# DM04r.net
KiCad netlist of a schematic drawn in EAGLE
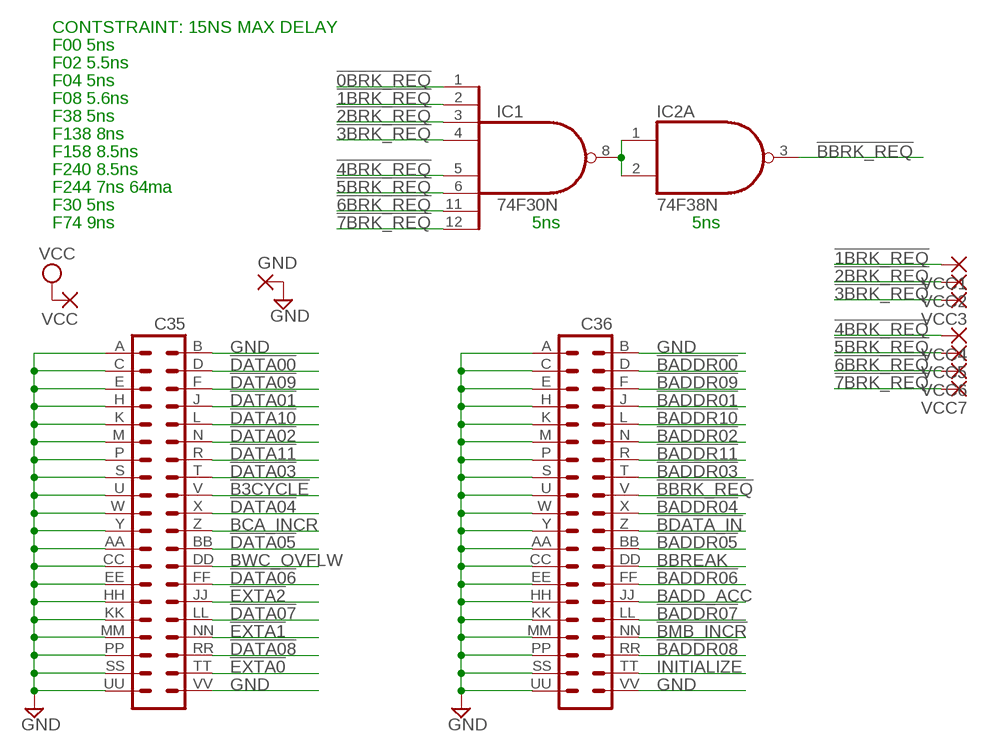
[diagram p0: schematic, sheet 1]
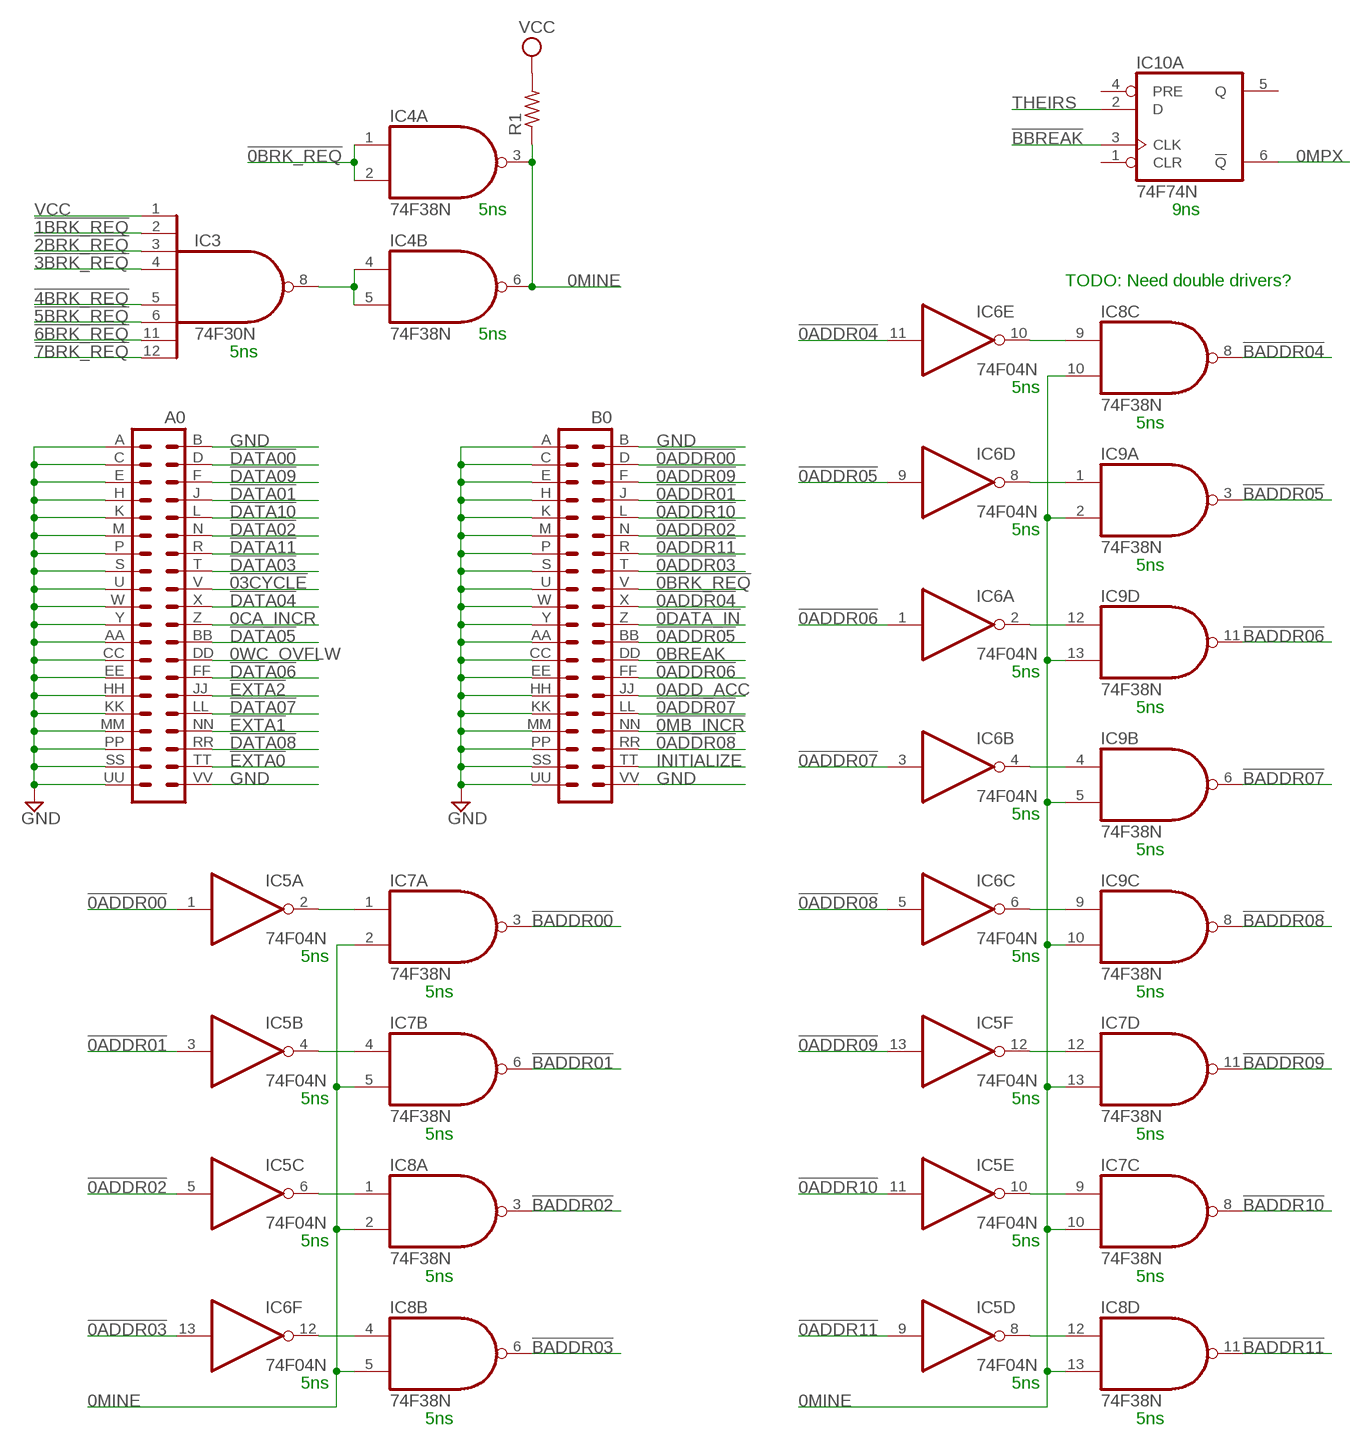
[diagram p1: schematic, sheet 2]

(export (version "E")
  (design (tool "Eeschema 10.0.6"))
  (components
    (comp (ref "C35")
      (value "DEC40PINV")
      (footprint "eagle-import:DEC40PINV")
      (libsource (lib "eagle-import") (part "DEC40PINV"))
    )
    (comp (ref "C36")
      (value "DEC40PINV")
      (footprint "eagle-import:DEC40PINV")
      (libsource (lib "eagle-import") (part "DEC40PINV"))
    )
    (comp (ref "GND")
      (value "2,54/0,8")
      (footprint "eagle-import:2,54_0,8")
      (libsource (lib "eagle-import") (part "2,54/0,8"))
    )
    (comp (ref "IC1")
      (value "74F30N")
      (footprint "eagle-import:DIL14")
      (libsource (lib "eagle-import") (part "7430NS"))
    )
    (comp (ref "IC2")
      (value "74F38N")
      (footprint "eagle-import:DIL14")
      (libsource (lib "eagle-import") (part "7438NF"))
    )
    (comp (ref "VCC")
      (value "2,54/0,8")
      (footprint "eagle-import:2,54_0,8")
      (libsource (lib "eagle-import") (part "2,54/0,8"))
    )
    (comp (ref "VCC1")
      (value "2,54/0,8")
      (footprint "eagle-import:2,54_0,8")
      (libsource (lib "eagle-import") (part "2,54/0,8"))
    )
    (comp (ref "VCC2")
      (value "2,54/0,8")
      (footprint "eagle-import:2,54_0,8")
      (libsource (lib "eagle-import") (part "2,54/0,8"))
    )
    (comp (ref "VCC3")
      (value "2,54/0,8")
      (footprint "eagle-import:2,54_0,8")
      (libsource (lib "eagle-import") (part "2,54/0,8"))
    )
    (comp (ref "VCC4")
      (value "2,54/0,8")
      (footprint "eagle-import:2,54_0,8")
      (libsource (lib "eagle-import") (part "2,54/0,8"))
    )
    (comp (ref "VCC5")
      (value "2,54/0,8")
      (footprint "eagle-import:2,54_0,8")
      (libsource (lib "eagle-import") (part "2,54/0,8"))
    )
    (comp (ref "VCC6")
      (value "2,54/0,8")
      (footprint "eagle-import:2,54_0,8")
      (libsource (lib "eagle-import") (part "2,54/0,8"))
    )
    (comp (ref "VCC7")
      (value "2,54/0,8")
      (footprint "eagle-import:2,54_0,8")
      (libsource (lib "eagle-import") (part "2,54/0,8"))
    )
    (comp (ref "A0")
      (value "DEC40PINV")
      (footprint "eagle-import:DEC40PINV")
      (libsource (lib "eagle-import") (part "DEC40PINV"))
    )
    (comp (ref "B0")
      (value "DEC40PINV")
      (footprint "eagle-import:DEC40PINV")
      (libsource (lib "eagle-import") (part "DEC40PINV"))
    )
    (comp (ref "IC3")
      (value "74F30N")
      (footprint "eagle-import:DIL14")
      (libsource (lib "eagle-import") (part "7430NS"))
    )
    (comp (ref "IC4")
      (value "74F38N")
      (footprint "eagle-import:DIL14")
      (libsource (lib "eagle-import") (part "7438NF"))
    )
    (comp (ref "IC5")
      (value "74F04N")
      (footprint "eagle-import:DIL14")
      (libsource (lib "eagle-import") (part "7404NS"))
    )
    (comp (ref "IC6")
      (value "74F04N")
      (footprint "eagle-import:DIL14")
      (libsource (lib "eagle-import") (part "7404NS"))
    )
    (comp (ref "IC7")
      (value "74F38N")
      (footprint "eagle-import:DIL14")
      (libsource (lib "eagle-import") (part "7438NF"))
    )
    (comp (ref "IC8")
      (value "74F38N")
      (footprint "eagle-import:DIL14")
      (libsource (lib "eagle-import") (part "7438NF"))
    )
    (comp (ref "IC9")
      (value "74F38N")
      (footprint "eagle-import:DIL14")
      (libsource (lib "eagle-import") (part "7438NF"))
    )
    (comp (ref "IC10")
      (value "74F74N")
      (footprint "eagle-import:DIL14")
      (libsource (lib "eagle-import") (part "7474NS"))
    )
    (comp (ref "R1")
      (value "R-US_0207/10")
      (footprint "eagle-import:0207_10")
      (libsource (lib "eagle-import") (part "R-US_0207/10"))
    )
  )
  (nets
    (net (code "1") (name "0ADD_ACC") (class "Default")
      (node (ref "B0") (pin "JJ") (pinfunction "30_JJ") (pintype "bidirectional"))
    )
    (net (code "2") (name "0BREAK") (class "Default")
      (node (ref "B0") (pin "DD") (pinfunction "26_DD") (pintype "bidirectional"))
    )
    (net (code "3") (name "0CA_INCR") (class "Default")
      (node (ref "A0") (pin "Z") (pinfunction "22_Z") (pintype "bidirectional"))
    )
    (net (code "4") (name "0MINE") (class "Default")
      (node (ref "IC4") (pin "3") (pinfunction "O_3") (pintype "open_collector"))
      (node (ref "IC4") (pin "6") (pinfunction "O_6") (pintype "open_collector"))
      (node (ref "IC7") (pin "10") (pinfunction "I1_10") (pintype "input"))
      (node (ref "IC7") (pin "13") (pinfunction "I1_13") (pintype "input"))
      (node (ref "IC7") (pin "2") (pinfunction "I1_2") (pintype "input"))
      (node (ref "IC7") (pin "5") (pinfunction "I1_5") (pintype "input"))
      (node (ref "IC8") (pin "10") (pinfunction "I1_10") (pintype "input"))
      (node (ref "IC8") (pin "13") (pinfunction "I1_13") (pintype "input"))
      (node (ref "IC8") (pin "2") (pinfunction "I1_2") (pintype "input"))
      (node (ref "IC8") (pin "5") (pinfunction "I1_5") (pintype "input"))
      (node (ref "IC9") (pin "10") (pinfunction "I1_10") (pintype "input"))
      (node (ref "IC9") (pin "13") (pinfunction "I1_13") (pintype "input"))
      (node (ref "IC9") (pin "2") (pinfunction "I1_2") (pintype "input"))
      (node (ref "IC9") (pin "5") (pinfunction "I1_5") (pintype "input"))
      (node (ref "R1") (pin "1") (pinfunction "1_1") (pintype "passive"))
    )
    (net (code "5") (name "0MPX") (class "Default")
      (node (ref "IC10") (pin "6") (pinfunction "~{Q}_6") (pintype "output"))
    )
    (net (code "6") (name "0WC_OVFLW") (class "Default")
      (node (ref "A0") (pin "DD") (pinfunction "26_DD") (pintype "bidirectional"))
    )
    (net (code "7") (name "BADD_ACC") (class "Default")
      (node (ref "C36") (pin "JJ") (pinfunction "30_JJ") (pintype "bidirectional"))
    )
    (net (code "8") (name "BBREAK") (class "Default")
      (node (ref "C36") (pin "DD") (pinfunction "26_DD") (pintype "bidirectional"))
    )
    (net (code "9") (name "BCA_INCR") (class "Default")
      (node (ref "C35") (pin "Z") (pinfunction "22_Z") (pintype "bidirectional"))
    )
    (net (code "10") (name "BWC_OVFLW") (class "Default")
      (node (ref "C35") (pin "DD") (pinfunction "26_DD") (pintype "bidirectional"))
    )
    (net (code "11") (name "GND") (class "Default")
      (node (ref "A0") (pin "A") (pinfunction "1_A") (pintype "bidirectional"))
      (node (ref "A0") (pin "AA") (pinfunction "23_AA") (pintype "bidirectional"))
      (node (ref "A0") (pin "B") (pinfunction "2_B") (pintype "bidirectional"))
      (node (ref "A0") (pin "C") (pinfunction "3_C") (pintype "bidirectional"))
      (node (ref "A0") (pin "CC") (pinfunction "25_CC") (pintype "bidirectional"))
      (node (ref "A0") (pin "E") (pinfunction "5_E") (pintype "bidirectional"))
      (node (ref "A0") (pin "EE") (pinfunction "27_EE") (pintype "bidirectional"))
      (node (ref "A0") (pin "H") (pinfunction "7_H") (pintype "bidirectional"))
      (node (ref "A0") (pin "HH") (pinfunction "29_HH") (pintype "bidirectional"))
      (node (ref "A0") (pin "K") (pinfunction "9_K") (pintype "bidirectional"))
      (node (ref "A0") (pin "KK") (pinfunction "31_KK") (pintype "bidirectional"))
      (node (ref "A0") (pin "M") (pinfunction "11_M") (pintype "bidirectional"))
      (node (ref "A0") (pin "MM") (pinfunction "33_MM") (pintype "bidirectional"))
      (node (ref "A0") (pin "P") (pinfunction "13_P") (pintype "bidirectional"))
      (node (ref "A0") (pin "PP") (pinfunction "35_PP") (pintype "bidirectional"))
      (node (ref "A0") (pin "S") (pinfunction "15_S") (pintype "bidirectional"))
      (node (ref "A0") (pin "SS") (pinfunction "37_SS") (pintype "bidirectional"))
      (node (ref "A0") (pin "U") (pinfunction "17_U") (pintype "bidirectional"))
      (node (ref "A0") (pin "UU") (pinfunction "39_UU") (pintype "bidirectional"))
      (node (ref "A0") (pin "VV") (pinfunction "40_VV") (pintype "bidirectional"))
      (node (ref "A0") (pin "W") (pinfunction "19_W") (pintype "bidirectional"))
      (node (ref "A0") (pin "Y") (pinfunction "21_Y") (pintype "bidirectional"))
      (node (ref "B0") (pin "A") (pinfunction "1_A") (pintype "bidirectional"))
      (node (ref "B0") (pin "AA") (pinfunction "23_AA") (pintype "bidirectional"))
      (node (ref "B0") (pin "B") (pinfunction "2_B") (pintype "bidirectional"))
      (node (ref "B0") (pin "C") (pinfunction "3_C") (pintype "bidirectional"))
      (node (ref "B0") (pin "CC") (pinfunction "25_CC") (pintype "bidirectional"))
      (node (ref "B0") (pin "E") (pinfunction "5_E") (pintype "bidirectional"))
      (node (ref "B0") (pin "EE") (pinfunction "27_EE") (pintype "bidirectional"))
      (node (ref "B0") (pin "H") (pinfunction "7_H") (pintype "bidirectional"))
      (node (ref "B0") (pin "HH") (pinfunction "29_HH") (pintype "bidirectional"))
      (node (ref "B0") (pin "K") (pinfunction "9_K") (pintype "bidirectional"))
      (node (ref "B0") (pin "KK") (pinfunction "31_KK") (pintype "bidirectional"))
      (node (ref "B0") (pin "M") (pinfunction "11_M") (pintype "bidirectional"))
      (node (ref "B0") (pin "MM") (pinfunction "33_MM") (pintype "bidirectional"))
      (node (ref "B0") (pin "P") (pinfunction "13_P") (pintype "bidirectional"))
      (node (ref "B0") (pin "PP") (pinfunction "35_PP") (pintype "bidirectional"))
      (node (ref "B0") (pin "S") (pinfunction "15_S") (pintype "bidirectional"))
      (node (ref "B0") (pin "SS") (pinfunction "37_SS") (pintype "bidirectional"))
      (node (ref "B0") (pin "U") (pinfunction "17_U") (pintype "bidirectional"))
      (node (ref "B0") (pin "UU") (pinfunction "39_UU") (pintype "bidirectional"))
      (node (ref "B0") (pin "VV") (pinfunction "40_VV") (pintype "bidirectional"))
      (node (ref "B0") (pin "W") (pinfunction "19_W") (pintype "bidirectional"))
      (node (ref "B0") (pin "Y") (pinfunction "21_Y") (pintype "bidirectional"))
      (node (ref "C35") (pin "A") (pinfunction "1_A") (pintype "bidirectional"))
      (node (ref "C35") (pin "AA") (pinfunction "23_AA") (pintype "bidirectional"))
      (node (ref "C35") (pin "B") (pinfunction "2_B") (pintype "bidirectional"))
      (node (ref "C35") (pin "C") (pinfunction "3_C") (pintype "bidirectional"))
      (node (ref "C35") (pin "CC") (pinfunction "25_CC") (pintype "bidirectional"))
      (node (ref "C35") (pin "E") (pinfunction "5_E") (pintype "bidirectional"))
      (node (ref "C35") (pin "EE") (pinfunction "27_EE") (pintype "bidirectional"))
      (node (ref "C35") (pin "H") (pinfunction "7_H") (pintype "bidirectional"))
      (node (ref "C35") (pin "HH") (pinfunction "29_HH") (pintype "bidirectional"))
      (node (ref "C35") (pin "K") (pinfunction "9_K") (pintype "bidirectional"))
      (node (ref "C35") (pin "KK") (pinfunction "31_KK") (pintype "bidirectional"))
      (node (ref "C35") (pin "M") (pinfunction "11_M") (pintype "bidirectional"))
      (node (ref "C35") (pin "MM") (pinfunction "33_MM") (pintype "bidirectional"))
      (node (ref "C35") (pin "P") (pinfunction "13_P") (pintype "bidirectional"))
      (node (ref "C35") (pin "PP") (pinfunction "35_PP") (pintype "bidirectional"))
      (node (ref "C35") (pin "S") (pinfunction "15_S") (pintype "bidirectional"))
      (node (ref "C35") (pin "SS") (pinfunction "37_SS") (pintype "bidirectional"))
      (node (ref "C35") (pin "U") (pinfunction "17_U") (pintype "bidirectional"))
      (node (ref "C35") (pin "UU") (pinfunction "39_UU") (pintype "bidirectional"))
      (node (ref "C35") (pin "VV") (pinfunction "40_VV") (pintype "bidirectional"))
      (node (ref "C35") (pin "W") (pinfunction "19_W") (pintype "bidirectional"))
      (node (ref "C35") (pin "Y") (pinfunction "21_Y") (pintype "bidirectional"))
      (node (ref "C36") (pin "A") (pinfunction "1_A") (pintype "bidirectional"))
      (node (ref "C36") (pin "AA") (pinfunction "23_AA") (pintype "bidirectional"))
      (node (ref "C36") (pin "B") (pinfunction "2_B") (pintype "bidirectional"))
      (node (ref "C36") (pin "C") (pinfunction "3_C") (pintype "bidirectional"))
      (node (ref "C36") (pin "CC") (pinfunction "25_CC") (pintype "bidirectional"))
      (node (ref "C36") (pin "E") (pinfunction "5_E") (pintype "bidirectional"))
      (node (ref "C36") (pin "EE") (pinfunction "27_EE") (pintype "bidirectional"))
      (node (ref "C36") (pin "H") (pinfunction "7_H") (pintype "bidirectional"))
      (node (ref "C36") (pin "HH") (pinfunction "29_HH") (pintype "bidirectional"))
      (node (ref "C36") (pin "K") (pinfunction "9_K") (pintype "bidirectional"))
      (node (ref "C36") (pin "KK") (pinfunction "31_KK") (pintype "bidirectional"))
      (node (ref "C36") (pin "M") (pinfunction "11_M") (pintype "bidirectional"))
      (node (ref "C36") (pin "MM") (pinfunction "33_MM") (pintype "bidirectional"))
      (node (ref "C36") (pin "P") (pinfunction "13_P") (pintype "bidirectional"))
      (node (ref "C36") (pin "PP") (pinfunction "35_PP") (pintype "bidirectional"))
      (node (ref "C36") (pin "S") (pinfunction "15_S") (pintype "bidirectional"))
      (node (ref "C36") (pin "SS") (pinfunction "37_SS") (pintype "bidirectional"))
      (node (ref "C36") (pin "U") (pinfunction "17_U") (pintype "bidirectional"))
      (node (ref "C36") (pin "UU") (pinfunction "39_UU") (pintype "bidirectional"))
      (node (ref "C36") (pin "VV") (pinfunction "40_VV") (pintype "bidirectional"))
      (node (ref "C36") (pin "W") (pinfunction "19_W") (pintype "bidirectional"))
      (node (ref "C36") (pin "Y") (pinfunction "21_Y") (pintype "bidirectional"))
      (node (ref "GND") (pin "1") (pinfunction "P_1") (pintype "passive"))
    )
    (net (code "12") (name "INITIALIZE") (class "Default")
      (node (ref "B0") (pin "TT") (pinfunction "38_TT") (pintype "bidirectional"))
      (node (ref "C36") (pin "TT") (pinfunction "38_TT") (pintype "bidirectional"))
    )
    (net (code "13") (name "Net-(IC1A-O)") (class "Default")
      (node (ref "IC1") (pin "8") (pinfunction "O_8") (pintype "output"))
      (node (ref "IC2") (pin "1") (pinfunction "I0_1") (pintype "input"))
      (node (ref "IC2") (pin "2") (pinfunction "I1_2") (pintype "input"))
    )
    (net (code "14") (name "Net-(IC3A-O)") (class "Default")
      (node (ref "IC3") (pin "8") (pinfunction "O_8") (pintype "output"))
      (node (ref "IC4") (pin "4") (pinfunction "I0_4") (pintype "input"))
      (node (ref "IC4") (pin "5") (pinfunction "I1_5") (pintype "input"))
    )
    (net (code "15") (name "Net-(IC5A-O)") (class "Default")
      (node (ref "IC5") (pin "2") (pinfunction "O_2") (pintype "output"))
      (node (ref "IC7") (pin "1") (pinfunction "I0_1") (pintype "input"))
    )
    (net (code "16") (name "Net-(IC5B-O)") (class "Default")
      (node (ref "IC5") (pin "4") (pinfunction "O_4") (pintype "output"))
      (node (ref "IC7") (pin "4") (pinfunction "I0_4") (pintype "input"))
    )
    (net (code "17") (name "Net-(IC5C-O)") (class "Default")
      (node (ref "IC5") (pin "6") (pinfunction "O_6") (pintype "output"))
      (node (ref "IC8") (pin "1") (pinfunction "I0_1") (pintype "input"))
    )
    (net (code "18") (name "Net-(IC5D-O)") (class "Default")
      (node (ref "IC5") (pin "8") (pinfunction "O_8") (pintype "output"))
      (node (ref "IC8") (pin "12") (pinfunction "I0_12") (pintype "input"))
    )
    (net (code "19") (name "Net-(IC5E-O)") (class "Default")
      (node (ref "IC5") (pin "10") (pinfunction "O_10") (pintype "output"))
      (node (ref "IC7") (pin "9") (pinfunction "I0_9") (pintype "input"))
    )
    (net (code "20") (name "Net-(IC5F-O)") (class "Default")
      (node (ref "IC5") (pin "12") (pinfunction "O_12") (pintype "output"))
      (node (ref "IC7") (pin "12") (pinfunction "I0_12") (pintype "input"))
    )
    (net (code "21") (name "Net-(IC6A-O)") (class "Default")
      (node (ref "IC6") (pin "2") (pinfunction "O_2") (pintype "output"))
      (node (ref "IC9") (pin "12") (pinfunction "I0_12") (pintype "input"))
    )
    (net (code "22") (name "Net-(IC6B-O)") (class "Default")
      (node (ref "IC6") (pin "4") (pinfunction "O_4") (pintype "output"))
      (node (ref "IC9") (pin "4") (pinfunction "I0_4") (pintype "input"))
    )
    (net (code "23") (name "Net-(IC6C-O)") (class "Default")
      (node (ref "IC6") (pin "6") (pinfunction "O_6") (pintype "output"))
      (node (ref "IC9") (pin "9") (pinfunction "I0_9") (pintype "input"))
    )
    (net (code "24") (name "Net-(IC6D-O)") (class "Default")
      (node (ref "IC6") (pin "8") (pinfunction "O_8") (pintype "output"))
      (node (ref "IC9") (pin "1") (pinfunction "I0_1") (pintype "input"))
    )
    (net (code "25") (name "Net-(IC6E-O)") (class "Default")
      (node (ref "IC6") (pin "10") (pinfunction "O_10") (pintype "output"))
      (node (ref "IC8") (pin "9") (pinfunction "I0_9") (pintype "input"))
    )
    (net (code "26") (name "Net-(IC6F-O)") (class "Default")
      (node (ref "IC6") (pin "12") (pinfunction "O_12") (pintype "output"))
      (node (ref "IC8") (pin "4") (pinfunction "I0_4") (pintype "input"))
    )
    (net (code "27") (name "THEIRS") (class "Default")
      (node (ref "IC10") (pin "2") (pinfunction "D_2") (pintype "input"))
    )
    (net (code "28") (name "VCC") (class "Default")
      (node (ref "IC3") (pin "1") (pinfunction "I0_1") (pintype "input"))
      (node (ref "R1") (pin "2") (pinfunction "2_2") (pintype "passive"))
      (node (ref "VCC") (pin "1") (pinfunction "P_1") (pintype "passive"))
    )
    (net (code "29") (name "unconnected-(IC10A-CLR-Pad1)") (class "Default")
      (node (ref "IC10") (pin "1") (pinfunction "CLR_1") (pintype "input"))
    )
    (net (code "30") (name "unconnected-(IC10A-PRE-Pad4)") (class "Default")
      (node (ref "IC10") (pin "4") (pinfunction "PRE_4") (pintype "input"))
    )
    (net (code "31") (name "unconnected-(IC10A-Q-Pad5)") (class "Default")
      (node (ref "IC10") (pin "5") (pinfunction "Q_5") (pintype "output"))
    )
    (net (code "32") (name "~{0ADDR00}") (class "Default")
      (node (ref "B0") (pin "D") (pinfunction "4_D") (pintype "bidirectional"))
      (node (ref "IC5") (pin "1") (pinfunction "I_1") (pintype "input"))
    )
    (net (code "33") (name "~{0ADDR01}") (class "Default")
      (node (ref "B0") (pin "J") (pinfunction "8_J") (pintype "bidirectional"))
      (node (ref "IC5") (pin "3") (pinfunction "I_3") (pintype "input"))
    )
    (net (code "34") (name "~{0ADDR02}") (class "Default")
      (node (ref "B0") (pin "N") (pinfunction "12_N") (pintype "bidirectional"))
      (node (ref "IC5") (pin "5") (pinfunction "I_5") (pintype "input"))
    )
    (net (code "35") (name "~{0ADDR03}") (class "Default")
      (node (ref "B0") (pin "T") (pinfunction "16_T") (pintype "bidirectional"))
      (node (ref "IC6") (pin "13") (pinfunction "I_13") (pintype "input"))
    )
    (net (code "36") (name "~{0ADDR04}") (class "Default")
      (node (ref "B0") (pin "X") (pinfunction "20_X") (pintype "bidirectional"))
      (node (ref "IC6") (pin "11") (pinfunction "I_11") (pintype "input"))
    )
    (net (code "37") (name "~{0ADDR05}") (class "Default")
      (node (ref "B0") (pin "BB") (pinfunction "24_BB") (pintype "bidirectional"))
      (node (ref "IC6") (pin "9") (pinfunction "I_9") (pintype "input"))
    )
    (net (code "38") (name "~{0ADDR06}") (class "Default")
      (node (ref "B0") (pin "FF") (pinfunction "28_FF") (pintype "bidirectional"))
      (node (ref "IC6") (pin "1") (pinfunction "I_1") (pintype "input"))
    )
    (net (code "39") (name "~{0ADDR07}") (class "Default")
      (node (ref "B0") (pin "LL") (pinfunction "32_LL") (pintype "bidirectional"))
      (node (ref "IC6") (pin "3") (pinfunction "I_3") (pintype "input"))
    )
    (net (code "40") (name "~{0ADDR08}") (class "Default")
      (node (ref "B0") (pin "RR") (pinfunction "36_RR") (pintype "bidirectional"))
      (node (ref "IC6") (pin "5") (pinfunction "I_5") (pintype "input"))
    )
    (net (code "41") (name "~{0ADDR09}") (class "Default")
      (node (ref "B0") (pin "F") (pinfunction "6_F") (pintype "bidirectional"))
      (node (ref "IC5") (pin "13") (pinfunction "I_13") (pintype "input"))
    )
    (net (code "42") (name "~{0ADDR10}") (class "Default")
      (node (ref "B0") (pin "L") (pinfunction "10_L") (pintype "bidirectional"))
      (node (ref "IC5") (pin "11") (pinfunction "I_11") (pintype "input"))
    )
    (net (code "43") (name "~{0ADDR11}") (class "Default")
      (node (ref "B0") (pin "R") (pinfunction "14_R") (pintype "bidirectional"))
      (node (ref "IC5") (pin "9") (pinfunction "I_9") (pintype "input"))
    )
    (net (code "44") (name "~{0BRK_REQ}") (class "Default")
      (node (ref "B0") (pin "V") (pinfunction "18_V") (pintype "bidirectional"))
      (node (ref "IC1") (pin "1") (pinfunction "I0_1") (pintype "input"))
      (node (ref "IC4") (pin "1") (pinfunction "I0_1") (pintype "input"))
      (node (ref "IC4") (pin "2") (pinfunction "I1_2") (pintype "input"))
    )
    (net (code "45") (name "~{0DATA_IN}") (class "Default")
      (node (ref "B0") (pin "Z") (pinfunction "22_Z") (pintype "bidirectional"))
    )
    (net (code "46") (name "~{0MB_INCR}") (class "Default")
      (node (ref "B0") (pin "NN") (pinfunction "34_NN") (pintype "bidirectional"))
    )
    (net (code "47") (name "~{1BRK_REQ}") (class "Default")
      (node (ref "IC1") (pin "2") (pinfunction "I1_2") (pintype "input"))
      (node (ref "IC3") (pin "2") (pinfunction "I1_2") (pintype "input"))
      (node (ref "VCC1") (pin "1") (pinfunction "P_1") (pintype "passive"))
    )
    (net (code "48") (name "~{2BRK_REQ}") (class "Default")
      (node (ref "IC1") (pin "3") (pinfunction "I2_3") (pintype "input"))
      (node (ref "IC3") (pin "3") (pinfunction "I2_3") (pintype "input"))
      (node (ref "VCC2") (pin "1") (pinfunction "P_1") (pintype "passive"))
    )
    (net (code "49") (name "~{3BRK_REQ}") (class "Default")
      (node (ref "IC1") (pin "4") (pinfunction "I3_4") (pintype "input"))
      (node (ref "IC3") (pin "4") (pinfunction "I3_4") (pintype "input"))
      (node (ref "VCC3") (pin "1") (pinfunction "P_1") (pintype "passive"))
    )
    (net (code "50") (name "~{03CYCLE}") (class "Default")
      (node (ref "A0") (pin "V") (pinfunction "18_V") (pintype "bidirectional"))
    )
    (net (code "51") (name "~{4BRK_REQ}") (class "Default")
      (node (ref "IC1") (pin "5") (pinfunction "I4_5") (pintype "input"))
      (node (ref "IC3") (pin "5") (pinfunction "I4_5") (pintype "input"))
      (node (ref "VCC4") (pin "1") (pinfunction "P_1") (pintype "passive"))
    )
    (net (code "52") (name "~{5BRK_REQ}") (class "Default")
      (node (ref "IC1") (pin "6") (pinfunction "I5_6") (pintype "input"))
      (node (ref "IC3") (pin "6") (pinfunction "I5_6") (pintype "input"))
      (node (ref "VCC5") (pin "1") (pinfunction "P_1") (pintype "passive"))
    )
    (net (code "53") (name "~{6BRK_REQ}") (class "Default")
      (node (ref "IC1") (pin "11") (pinfunction "I6_11") (pintype "input"))
      (node (ref "IC3") (pin "11") (pinfunction "I6_11") (pintype "input"))
      (node (ref "VCC6") (pin "1") (pinfunction "P_1") (pintype "passive"))
    )
    (net (code "54") (name "~{7BRK_REQ}") (class "Default")
      (node (ref "IC1") (pin "12") (pinfunction "I7_12") (pintype "input"))
      (node (ref "IC3") (pin "12") (pinfunction "I7_12") (pintype "input"))
      (node (ref "VCC7") (pin "1") (pinfunction "P_1") (pintype "passive"))
    )
    (net (code "55") (name "~{B3CYCLE}") (class "Default")
      (node (ref "C35") (pin "V") (pinfunction "18_V") (pintype "bidirectional"))
    )
    (net (code "56") (name "~{BADDR00}") (class "Default")
      (node (ref "C36") (pin "D") (pinfunction "4_D") (pintype "bidirectional"))
      (node (ref "IC7") (pin "3") (pinfunction "O_3") (pintype "open_collector"))
    )
    (net (code "57") (name "~{BADDR01}") (class "Default")
      (node (ref "C36") (pin "J") (pinfunction "8_J") (pintype "bidirectional"))
      (node (ref "IC7") (pin "6") (pinfunction "O_6") (pintype "open_collector"))
    )
    (net (code "58") (name "~{BADDR02}") (class "Default")
      (node (ref "C36") (pin "N") (pinfunction "12_N") (pintype "bidirectional"))
      (node (ref "IC8") (pin "3") (pinfunction "O_3") (pintype "open_collector"))
    )
    (net (code "59") (name "~{BADDR03}") (class "Default")
      (node (ref "C36") (pin "T") (pinfunction "16_T") (pintype "bidirectional"))
      (node (ref "IC8") (pin "6") (pinfunction "O_6") (pintype "open_collector"))
    )
    (net (code "60") (name "~{BADDR04}") (class "Default")
      (node (ref "C36") (pin "X") (pinfunction "20_X") (pintype "bidirectional"))
      (node (ref "IC8") (pin "8") (pinfunction "O_8") (pintype "open_collector"))
    )
    (net (code "61") (name "~{BADDR05}") (class "Default")
      (node (ref "C36") (pin "BB") (pinfunction "24_BB") (pintype "bidirectional"))
      (node (ref "IC9") (pin "3") (pinfunction "O_3") (pintype "open_collector"))
    )
    (net (code "62") (name "~{BADDR06}") (class "Default")
      (node (ref "C36") (pin "FF") (pinfunction "28_FF") (pintype "bidirectional"))
      (node (ref "IC9") (pin "11") (pinfunction "O_11") (pintype "open_collector"))
    )
    (net (code "63") (name "~{BADDR07}") (class "Default")
      (node (ref "C36") (pin "LL") (pinfunction "32_LL") (pintype "bidirectional"))
      (node (ref "IC9") (pin "6") (pinfunction "O_6") (pintype "open_collector"))
    )
    (net (code "64") (name "~{BADDR08}") (class "Default")
      (node (ref "C36") (pin "RR") (pinfunction "36_RR") (pintype "bidirectional"))
      (node (ref "IC9") (pin "8") (pinfunction "O_8") (pintype "open_collector"))
    )
    (net (code "65") (name "~{BADDR09}") (class "Default")
      (node (ref "C36") (pin "F") (pinfunction "6_F") (pintype "bidirectional"))
      (node (ref "IC7") (pin "11") (pinfunction "O_11") (pintype "open_collector"))
    )
    (net (code "66") (name "~{BADDR10}") (class "Default")
      (node (ref "C36") (pin "L") (pinfunction "10_L") (pintype "bidirectional"))
      (node (ref "IC7") (pin "8") (pinfunction "O_8") (pintype "open_collector"))
    )
    (net (code "67") (name "~{BADDR11}") (class "Default")
      (node (ref "C36") (pin "R") (pinfunction "14_R") (pintype "bidirectional"))
      (node (ref "IC8") (pin "11") (pinfunction "O_11") (pintype "open_collector"))
    )
    (net (code "68") (name "~{BBREAK}") (class "Default")
      (node (ref "IC10") (pin "3") (pinfunction "CLK_3") (pintype "input"))
    )
    (net (code "69") (name "~{BBRK_REQ}") (class "Default")
      (node (ref "C36") (pin "V") (pinfunction "18_V") (pintype "bidirectional"))
      (node (ref "IC2") (pin "3") (pinfunction "O_3") (pintype "open_collector"))
    )
    (net (code "70") (name "~{BDATA_IN}") (class "Default")
      (node (ref "C36") (pin "Z") (pinfunction "22_Z") (pintype "bidirectional"))
    )
    (net (code "71") (name "~{BMB_INCR}") (class "Default")
      (node (ref "C36") (pin "NN") (pinfunction "34_NN") (pintype "bidirectional"))
    )
    (net (code "72") (name "~{DATA00}") (class "Default")
      (node (ref "A0") (pin "D") (pinfunction "4_D") (pintype "bidirectional"))
      (node (ref "C35") (pin "D") (pinfunction "4_D") (pintype "bidirectional"))
    )
    (net (code "73") (name "~{DATA01}") (class "Default")
      (node (ref "A0") (pin "J") (pinfunction "8_J") (pintype "bidirectional"))
      (node (ref "C35") (pin "J") (pinfunction "8_J") (pintype "bidirectional"))
    )
    (net (code "74") (name "~{DATA02}") (class "Default")
      (node (ref "A0") (pin "N") (pinfunction "12_N") (pintype "bidirectional"))
      (node (ref "C35") (pin "N") (pinfunction "12_N") (pintype "bidirectional"))
    )
    (net (code "75") (name "~{DATA03}") (class "Default")
      (node (ref "A0") (pin "T") (pinfunction "16_T") (pintype "bidirectional"))
      (node (ref "C35") (pin "T") (pinfunction "16_T") (pintype "bidirectional"))
    )
    (net (code "76") (name "~{DATA04}") (class "Default")
      (node (ref "A0") (pin "X") (pinfunction "20_X") (pintype "bidirectional"))
      (node (ref "C35") (pin "X") (pinfunction "20_X") (pintype "bidirectional"))
    )
    (net (code "77") (name "~{DATA05}") (class "Default")
      (node (ref "A0") (pin "BB") (pinfunction "24_BB") (pintype "bidirectional"))
      (node (ref "C35") (pin "BB") (pinfunction "24_BB") (pintype "bidirectional"))
    )
    (net (code "78") (name "~{DATA06}") (class "Default")
      (node (ref "A0") (pin "FF") (pinfunction "28_FF") (pintype "bidirectional"))
      (node (ref "C35") (pin "FF") (pinfunction "28_FF") (pintype "bidirectional"))
    )
    (net (code "79") (name "~{DATA07}") (class "Default")
      (node (ref "A0") (pin "LL") (pinfunction "32_LL") (pintype "bidirectional"))
      (node (ref "C35") (pin "LL") (pinfunction "32_LL") (pintype "bidirectional"))
    )
    (net (code "80") (name "~{DATA08}") (class "Default")
      (node (ref "A0") (pin "RR") (pinfunction "36_RR") (pintype "bidirectional"))
      (node (ref "C35") (pin "RR") (pinfunction "36_RR") (pintype "bidirectional"))
    )
    (net (code "81") (name "~{DATA09}") (class "Default")
      (node (ref "A0") (pin "F") (pinfunction "6_F") (pintype "bidirectional"))
      (node (ref "C35") (pin "F") (pinfunction "6_F") (pintype "bidirectional"))
    )
    (net (code "82") (name "~{DATA10}") (class "Default")
      (node (ref "A0") (pin "L") (pinfunction "10_L") (pintype "bidirectional"))
      (node (ref "C35") (pin "L") (pinfunction "10_L") (pintype "bidirectional"))
    )
    (net (code "83") (name "~{DATA11}") (class "Default")
      (node (ref "A0") (pin "R") (pinfunction "14_R") (pintype "bidirectional"))
      (node (ref "C35") (pin "R") (pinfunction "14_R") (pintype "bidirectional"))
    )
    (net (code "84") (name "~{EXTA0}") (class "Default")
      (node (ref "A0") (pin "TT") (pinfunction "38_TT") (pintype "bidirectional"))
      (node (ref "C35") (pin "TT") (pinfunction "38_TT") (pintype "bidirectional"))
    )
    (net (code "85") (name "~{EXTA1}") (class "Default")
      (node (ref "A0") (pin "NN") (pinfunction "34_NN") (pintype "bidirectional"))
      (node (ref "C35") (pin "NN") (pinfunction "34_NN") (pintype "bidirectional"))
    )
    (net (code "86") (name "~{EXTA2}") (class "Default")
      (node (ref "A0") (pin "JJ") (pinfunction "30_JJ") (pintype "bidirectional"))
      (node (ref "C35") (pin "JJ") (pinfunction "30_JJ") (pintype "bidirectional"))
    )
  )
)
